# schematic.net
KiCad netlist of a schematic drawn in EAGLE
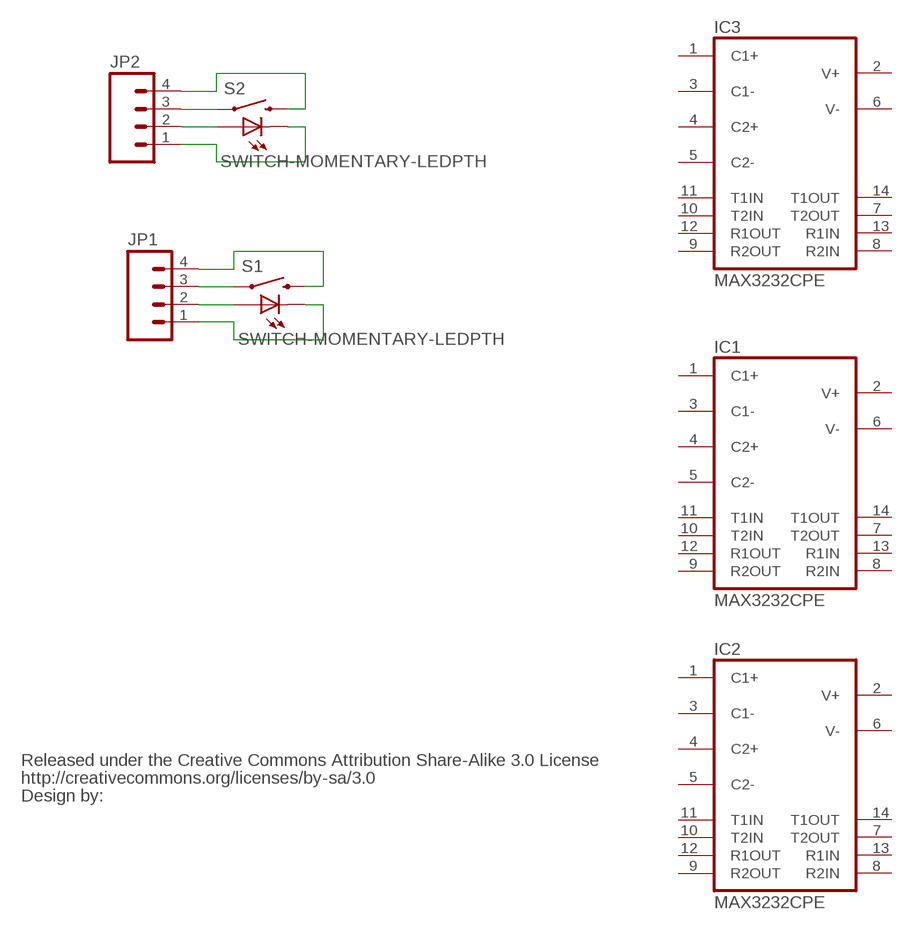
[diagram p0: schematic, sheet 1]

(export (version "E")
  (design (tool "Eeschema 10.0.6"))
  (components
    (comp (ref "CC_TEXT1")
      (value "CREATIVE_COMMONS")
      (footprint "eagle-import:CREATIVE_COMMONS")
      (libsource (lib "eagle-import") (part "CREATIVE_COMMONS"))
    )
    (comp (ref "IC1")
      (value "MAX3232CPE")
      (footprint "eagle-import:DIL16")
      (fields (field (name "MF") "MAXIM") (field (name "MPN") "MAX3232CPE+"))
      (libsource (lib "eagle-import") (part "MAX3232PEC"))
    )
    (comp (ref "IC2")
      (value "MAX3232CPE")
      (footprint "eagle-import:DIL16")
      (fields (field (name "MF") "MAXIM") (field (name "MPN") "MAX3232CPE+"))
      (libsource (lib "eagle-import") (part "MAX3232PEC"))
    )
    (comp (ref "IC3")
      (value "MAX3232CPE")
      (footprint "eagle-import:DIL16")
      (fields (field (name "MF") "MAXIM") (field (name "MPN") "MAX3232CPE+"))
      (libsource (lib "eagle-import") (part "MAX3232PEC"))
    )
    (comp (ref "JP1")
      (value "M04PTH")
      (footprint "eagle-import:1X04")
      (libsource (lib "eagle-import") (part "M04PTH"))
    )
    (comp (ref "JP2")
      (value "M04PTH")
      (footprint "eagle-import:1X04")
      (libsource (lib "eagle-import") (part "M04PTH"))
    )
    (comp (ref "S1")
      (value "SWITCH-MOMENTARY-LEDPTH")
      (footprint "eagle-import:TACTILE-PTH-LED-12MM")
      (libsource (lib "eagle-import") (part "SWITCH-MOMENTARY-LEDPTH"))
    )
    (comp (ref "S2")
      (value "SWITCH-MOMENTARY-LEDPTH")
      (footprint "eagle-import:TACTILE-PTH-LED-12MM")
      (libsource (lib "eagle-import") (part "SWITCH-MOMENTARY-LEDPTH"))
    )
  )
  (nets
    (net (code "1") (name "Net-(JP1-Pad1)") (class "Default")
      (node (ref "JP1") (pin "1") (pinfunction "1_1") (pintype "passive"))
      (node (ref "S1") (pin "C") (pinfunction "C_C") (pintype "passive"))
    )
    (net (code "2") (name "Net-(JP1-Pad2)") (class "Default")
      (node (ref "JP1") (pin "2") (pinfunction "2_2") (pintype "passive"))
      (node (ref "S1") (pin "A") (pinfunction "A_A") (pintype "passive"))
    )
    (net (code "3") (name "Net-(JP1-Pad4)") (class "Default")
      (node (ref "JP1") (pin "4") (pinfunction "4_4") (pintype "passive"))
      (node (ref "S1") (pin "2") (pinfunction "2_2") (pintype "passive"))
    )
    (net (code "4") (name "Net-(JP2-Pad1)") (class "Default")
      (node (ref "JP2") (pin "1") (pinfunction "1_1") (pintype "passive"))
      (node (ref "S2") (pin "C") (pinfunction "C_C") (pintype "passive"))
    )
    (net (code "5") (name "Net-(JP2-Pad2)") (class "Default")
      (node (ref "JP2") (pin "2") (pinfunction "2_2") (pintype "passive"))
      (node (ref "S2") (pin "A") (pinfunction "A_A") (pintype "passive"))
    )
    (net (code "6") (name "Net-(JP2-Pad4)") (class "Default")
      (node (ref "JP2") (pin "4") (pinfunction "4_4") (pintype "passive"))
      (node (ref "S2") (pin "2") (pinfunction "2_2") (pintype "passive"))
    )
    (net (code "7") (name "Net-(S1-1)") (class "Default")
      (node (ref "JP1") (pin "3") (pinfunction "3_3") (pintype "passive"))
      (node (ref "S1") (pin "4") (pinfunction "1_4") (pintype "passive"))
    )
    (net (code "8") (name "Net-(S2-1)") (class "Default")
      (node (ref "JP2") (pin "3") (pinfunction "3_3") (pintype "passive"))
      (node (ref "S2") (pin "4") (pinfunction "1_4") (pintype "passive"))
    )
    (net (code "9") (name "unconnected-(IC1A-C1+-Pad1)") (class "Default")
      (node (ref "IC1") (pin "1") (pinfunction "C1+_1") (pintype "bidirectional"))
    )
    (net (code "10") (name "unconnected-(IC1A-C1--Pad3)") (class "Default")
      (node (ref "IC1") (pin "3") (pinfunction "C1-_3") (pintype "bidirectional"))
    )
    (net (code "11") (name "unconnected-(IC1A-C2+-Pad4)") (class "Default")
      (node (ref "IC1") (pin "4") (pinfunction "C2+_4") (pintype "bidirectional"))
    )
    (net (code "12") (name "unconnected-(IC1A-C2--Pad5)") (class "Default")
      (node (ref "IC1") (pin "5") (pinfunction "C2-_5") (pintype "bidirectional"))
    )
    (net (code "13") (name "unconnected-(IC1A-R1IN-Pad13)") (class "Default")
      (node (ref "IC1") (pin "13") (pinfunction "R1IN_13") (pintype "input"))
    )
    (net (code "14") (name "unconnected-(IC1A-R1OUT-Pad12)") (class "Default")
      (node (ref "IC1") (pin "12") (pinfunction "R1OUT_12") (pintype "output"))
    )
    (net (code "15") (name "unconnected-(IC1A-R2IN-Pad8)") (class "Default")
      (node (ref "IC1") (pin "8") (pinfunction "R2IN_8") (pintype "input"))
    )
    (net (code "16") (name "unconnected-(IC1A-R2OUT-Pad9)") (class "Default")
      (node (ref "IC1") (pin "9") (pinfunction "R2OUT_9") (pintype "output"))
    )
    (net (code "17") (name "unconnected-(IC1A-T1IN-Pad11)") (class "Default")
      (node (ref "IC1") (pin "11") (pinfunction "T1IN_11") (pintype "input"))
    )
    (net (code "18") (name "unconnected-(IC1A-T1OUT-Pad14)") (class "Default")
      (node (ref "IC1") (pin "14") (pinfunction "T1OUT_14") (pintype "output"))
    )
    (net (code "19") (name "unconnected-(IC1A-T2IN-Pad10)") (class "Default")
      (node (ref "IC1") (pin "10") (pinfunction "T2IN_10") (pintype "input"))
    )
    (net (code "20") (name "unconnected-(IC1A-T2OUT-Pad7)") (class "Default")
      (node (ref "IC1") (pin "7") (pinfunction "T2OUT_7") (pintype "output"))
    )
    (net (code "21") (name "unconnected-(IC1A-V+-Pad2)") (class "Default")
      (node (ref "IC1") (pin "2") (pinfunction "V+_2") (pintype "bidirectional"))
    )
    (net (code "22") (name "unconnected-(IC1A-V--Pad6)") (class "Default")
      (node (ref "IC1") (pin "6") (pinfunction "V-_6") (pintype "bidirectional"))
    )
    (net (code "23") (name "unconnected-(IC2A-C1+-Pad1)") (class "Default")
      (node (ref "IC2") (pin "1") (pinfunction "C1+_1") (pintype "bidirectional"))
    )
    (net (code "24") (name "unconnected-(IC2A-C1--Pad3)") (class "Default")
      (node (ref "IC2") (pin "3") (pinfunction "C1-_3") (pintype "bidirectional"))
    )
    (net (code "25") (name "unconnected-(IC2A-C2+-Pad4)") (class "Default")
      (node (ref "IC2") (pin "4") (pinfunction "C2+_4") (pintype "bidirectional"))
    )
    (net (code "26") (name "unconnected-(IC2A-C2--Pad5)") (class "Default")
      (node (ref "IC2") (pin "5") (pinfunction "C2-_5") (pintype "bidirectional"))
    )
    (net (code "27") (name "unconnected-(IC2A-R1IN-Pad13)") (class "Default")
      (node (ref "IC2") (pin "13") (pinfunction "R1IN_13") (pintype "input"))
    )
    (net (code "28") (name "unconnected-(IC2A-R1OUT-Pad12)") (class "Default")
      (node (ref "IC2") (pin "12") (pinfunction "R1OUT_12") (pintype "output"))
    )
    (net (code "29") (name "unconnected-(IC2A-R2IN-Pad8)") (class "Default")
      (node (ref "IC2") (pin "8") (pinfunction "R2IN_8") (pintype "input"))
    )
    (net (code "30") (name "unconnected-(IC2A-R2OUT-Pad9)") (class "Default")
      (node (ref "IC2") (pin "9") (pinfunction "R2OUT_9") (pintype "output"))
    )
    (net (code "31") (name "unconnected-(IC2A-T1IN-Pad11)") (class "Default")
      (node (ref "IC2") (pin "11") (pinfunction "T1IN_11") (pintype "input"))
    )
    (net (code "32") (name "unconnected-(IC2A-T1OUT-Pad14)") (class "Default")
      (node (ref "IC2") (pin "14") (pinfunction "T1OUT_14") (pintype "output"))
    )
    (net (code "33") (name "unconnected-(IC2A-T2IN-Pad10)") (class "Default")
      (node (ref "IC2") (pin "10") (pinfunction "T2IN_10") (pintype "input"))
    )
    (net (code "34") (name "unconnected-(IC2A-T2OUT-Pad7)") (class "Default")
      (node (ref "IC2") (pin "7") (pinfunction "T2OUT_7") (pintype "output"))
    )
    (net (code "35") (name "unconnected-(IC2A-V+-Pad2)") (class "Default")
      (node (ref "IC2") (pin "2") (pinfunction "V+_2") (pintype "bidirectional"))
    )
    (net (code "36") (name "unconnected-(IC2A-V--Pad6)") (class "Default")
      (node (ref "IC2") (pin "6") (pinfunction "V-_6") (pintype "bidirectional"))
    )
    (net (code "37") (name "unconnected-(IC3A-C1+-Pad1)") (class "Default")
      (node (ref "IC3") (pin "1") (pinfunction "C1+_1") (pintype "bidirectional"))
    )
    (net (code "38") (name "unconnected-(IC3A-C1--Pad3)") (class "Default")
      (node (ref "IC3") (pin "3") (pinfunction "C1-_3") (pintype "bidirectional"))
    )
    (net (code "39") (name "unconnected-(IC3A-C2+-Pad4)") (class "Default")
      (node (ref "IC3") (pin "4") (pinfunction "C2+_4") (pintype "bidirectional"))
    )
    (net (code "40") (name "unconnected-(IC3A-C2--Pad5)") (class "Default")
      (node (ref "IC3") (pin "5") (pinfunction "C2-_5") (pintype "bidirectional"))
    )
    (net (code "41") (name "unconnected-(IC3A-R1IN-Pad13)") (class "Default")
      (node (ref "IC3") (pin "13") (pinfunction "R1IN_13") (pintype "input"))
    )
    (net (code "42") (name "unconnected-(IC3A-R1OUT-Pad12)") (class "Default")
      (node (ref "IC3") (pin "12") (pinfunction "R1OUT_12") (pintype "output"))
    )
    (net (code "43") (name "unconnected-(IC3A-R2IN-Pad8)") (class "Default")
      (node (ref "IC3") (pin "8") (pinfunction "R2IN_8") (pintype "input"))
    )
    (net (code "44") (name "unconnected-(IC3A-R2OUT-Pad9)") (class "Default")
      (node (ref "IC3") (pin "9") (pinfunction "R2OUT_9") (pintype "output"))
    )
    (net (code "45") (name "unconnected-(IC3A-T1IN-Pad11)") (class "Default")
      (node (ref "IC3") (pin "11") (pinfunction "T1IN_11") (pintype "input"))
    )
    (net (code "46") (name "unconnected-(IC3A-T1OUT-Pad14)") (class "Default")
      (node (ref "IC3") (pin "14") (pinfunction "T1OUT_14") (pintype "output"))
    )
    (net (code "47") (name "unconnected-(IC3A-T2IN-Pad10)") (class "Default")
      (node (ref "IC3") (pin "10") (pinfunction "T2IN_10") (pintype "input"))
    )
    (net (code "48") (name "unconnected-(IC3A-T2OUT-Pad7)") (class "Default")
      (node (ref "IC3") (pin "7") (pinfunction "T2OUT_7") (pintype "output"))
    )
    (net (code "49") (name "unconnected-(IC3A-V+-Pad2)") (class "Default")
      (node (ref "IC3") (pin "2") (pinfunction "V+_2") (pintype "bidirectional"))
    )
    (net (code "50") (name "unconnected-(IC3A-V--Pad6)") (class "Default")
      (node (ref "IC3") (pin "6") (pinfunction "V-_6") (pintype "bidirectional"))
    )
  )
)
